# rf_exca.net
KiCad netlist of a schematic drawn in EAGLE
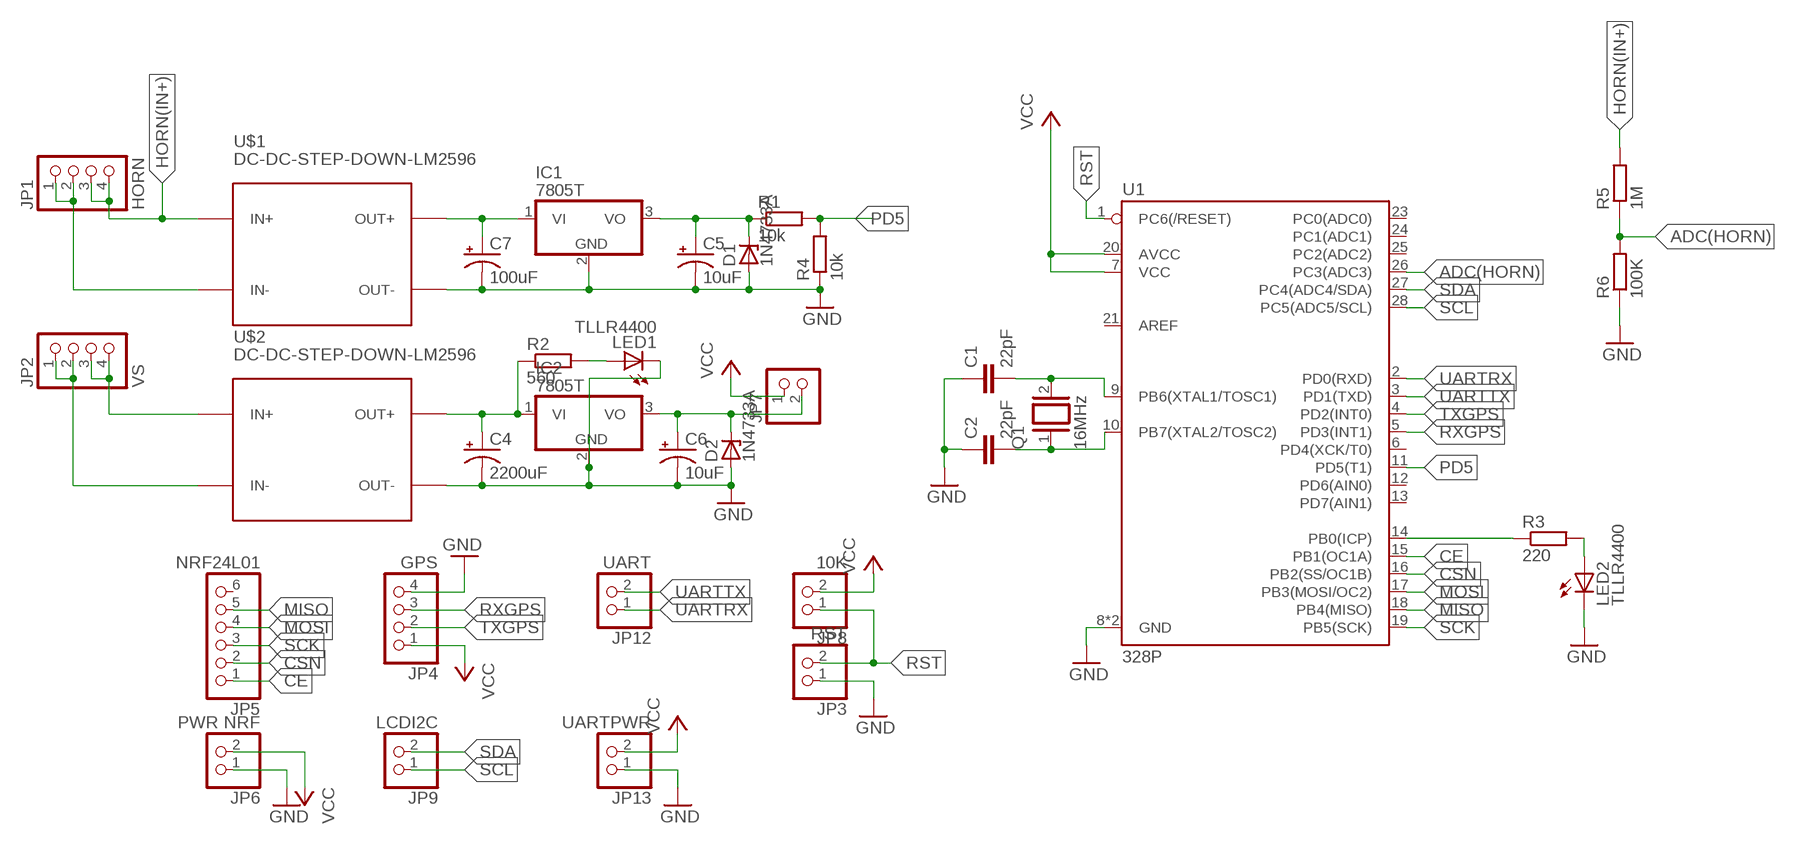
[diagram p0: schematic, sheet 1]

(export (version "E")
  (design (tool "Eeschema 10.0.6"))
  (components
    (comp (ref "C1")
      (value "22pF")
      (footprint "eagle-import:C025-024X044")
      (libsource (lib "eagle-import") (part "C-EU025-024X044"))
    )
    (comp (ref "C2")
      (value "22pF")
      (footprint "eagle-import:C025-024X044")
      (libsource (lib "eagle-import") (part "C-EU025-024X044"))
    )
    (comp (ref "C4")
      (value "2200uF")
      (footprint "eagle-import:E5-13")
      (libsource (lib "eagle-import") (part "CPOL-USE5-13"))
    )
    (comp (ref "C5")
      (value "10uF")
      (footprint "eagle-import:E2,5-6E")
      (libsource (lib "eagle-import") (part "CPOL-USE2,5-6E"))
    )
    (comp (ref "C6")
      (value "10uF")
      (footprint "eagle-import:E2,5-6E")
      (libsource (lib "eagle-import") (part "CPOL-USE2,5-6E"))
    )
    (comp (ref "C7")
      (value "100uF")
      (footprint "eagle-import:E2,5-7")
      (libsource (lib "eagle-import") (part "CPOL-USE2.5-7"))
    )
    (comp (ref "D1")
      (value "1N4733A")
      (footprint "eagle-import:DO41Z10")
      (libsource (lib "eagle-import") (part "1N4728"))
    )
    (comp (ref "D2")
      (value "1N4733A")
      (footprint "eagle-import:DO41Z10")
      (libsource (lib "eagle-import") (part "1N4728"))
    )
    (comp (ref "IC1")
      (value "7805T")
      (footprint "eagle-import:TO220H")
      (libsource (lib "eagle-import") (part "78T05"))
    )
    (comp (ref "IC2")
      (value "7805T")
      (footprint "eagle-import:TO220H")
      (libsource (lib "eagle-import") (part "78T05"))
    )
    (comp (ref "JP1")
      (value "HORN")
      (footprint "eagle-import:1X04")
      (libsource (lib "eagle-import") (part "PINHD-1X4"))
    )
    (comp (ref "JP2")
      (value "VS")
      (footprint "eagle-import:1X04")
      (libsource (lib "eagle-import") (part "PINHD-1X4"))
    )
    (comp (ref "JP3")
      (value "RST")
      (footprint "eagle-import:1X02")
      (libsource (lib "eagle-import") (part "PINHD-1X2"))
    )
    (comp (ref "JP4")
      (value "GPS")
      (footprint "eagle-import:1X04")
      (libsource (lib "eagle-import") (part "PINHD-1X4"))
    )
    (comp (ref "JP5")
      (value "NRF24L01")
      (footprint "eagle-import:1X06")
      (libsource (lib "eagle-import") (part "PINHD-1X6"))
    )
    (comp (ref "JP6")
      (value "PWR NRF")
      (footprint "eagle-import:1X02")
      (libsource (lib "eagle-import") (part "PINHD-1X2"))
    )
    (comp (ref "JP7")
      (value "PINHD-1X2")
      (footprint "eagle-import:1X02")
      (libsource (lib "eagle-import") (part "PINHD-1X2"))
    )
    (comp (ref "JP8")
      (value "10K")
      (footprint "eagle-import:1X02")
      (libsource (lib "eagle-import") (part "PINHD-1X2"))
    )
    (comp (ref "JP9")
      (value "LCDI2C")
      (footprint "eagle-import:1X02")
      (libsource (lib "eagle-import") (part "PINHD-1X2"))
    )
    (comp (ref "JP12")
      (value "UART")
      (footprint "eagle-import:1X02")
      (libsource (lib "eagle-import") (part "PINHD-1X2"))
    )
    (comp (ref "JP13")
      (value "UARTPWR")
      (footprint "eagle-import:1X02")
      (libsource (lib "eagle-import") (part "PINHD-1X2"))
    )
    (comp (ref "LED1")
      (value "TLLR4400")
      (footprint "eagle-import:LED3MM")
      (fields (field (name "MF") "VISHAY SEMICONDUCTOR"))
      (libsource (lib "eagle-import") (part "TLLR4400"))
    )
    (comp (ref "LED2")
      (value "TLLR4400")
      (footprint "eagle-import:LED3MM")
      (fields (field (name "MF") "VISHAY SEMICONDUCTOR"))
      (libsource (lib "eagle-import") (part "TLLR4400"))
    )
    (comp (ref "Q1")
      (value "16MHz")
      (footprint "eagle-import:QS")
      (libsource (lib "eagle-import") (part "XTAL/S"))
    )
    (comp (ref "R1")
      (value "10k")
      (footprint "eagle-import:0207_12")
      (libsource (lib "eagle-import") (part "R-EU_0207/12"))
    )
    (comp (ref "R2")
      (value "560")
      (footprint "eagle-import:0207_12")
      (libsource (lib "eagle-import") (part "R-EU_0207/12"))
    )
    (comp (ref "R3")
      (value "220")
      (footprint "eagle-import:0207_12")
      (libsource (lib "eagle-import") (part "R-EU_0207/12"))
    )
    (comp (ref "R4")
      (value "10k")
      (footprint "eagle-import:0207_12")
      (libsource (lib "eagle-import") (part "R-EU_0207/12"))
    )
    (comp (ref "R5")
      (value "1M")
      (footprint "eagle-import:0207_12")
      (libsource (lib "eagle-import") (part "R-EU_0207/12"))
    )
    (comp (ref "R6")
      (value "100K")
      (footprint "eagle-import:0207_12")
      (libsource (lib "eagle-import") (part "R-EU_0207/12"))
    )
    (comp (ref "U$1")
      (value "DC-DC-STEP-DOWN-LM2596")
      (footprint "eagle-import:DC-DC-STEP-DOWN-LM2596")
      (libsource (lib "eagle-import") (part "DC-DC-STEP-DOWN-LM2596"))
    )
    (comp (ref "U$2")
      (value "DC-DC-STEP-DOWN-LM2596")
      (footprint "eagle-import:DC-DC-STEP-DOWN-LM2596")
      (libsource (lib "eagle-import") (part "DC-DC-STEP-DOWN-LM2596"))
    )
    (comp (ref "U1")
      (value "328P")
      (footprint "eagle-import:DIP28")
      (libsource (lib "eagle-import") (part "ATMEGA328P_PDIP"))
    )
  )
  (nets
    (net (code "1") (name "ADC(HORN)") (class "Default")
      (node (ref "R5") (pin "1") (pinfunction "1_1") (pintype "passive"))
      (node (ref "R6") (pin "2") (pinfunction "2_2") (pintype "passive"))
      (node (ref "U1") (pin "26") (pinfunction "PC3(ADC3)_26") (pintype "bidirectional"))
    )
    (net (code "2") (name "CE") (class "Default")
      (node (ref "JP5") (pin "1") (pinfunction "1_1") (pintype "passive"))
      (node (ref "U1") (pin "15") (pinfunction "PB1(OC1A)_15") (pintype "bidirectional"))
    )
    (net (code "3") (name "CSN") (class "Default")
      (node (ref "JP5") (pin "2") (pinfunction "2_2") (pintype "passive"))
      (node (ref "U1") (pin "16") (pinfunction "PB2(SS/OC1B)_16") (pintype "bidirectional"))
    )
    (net (code "4") (name "GND") (class "Default")
      (node (ref "C1") (pin "1") (pinfunction "1_1") (pintype "passive"))
      (node (ref "C2") (pin "1") (pinfunction "1_1") (pintype "passive"))
      (node (ref "C4") (pin "-") (pinfunction "-_-") (pintype "passive"))
      (node (ref "C5") (pin "-") (pinfunction "-_-") (pintype "passive"))
      (node (ref "C6") (pin "-") (pinfunction "-_-") (pintype "passive"))
      (node (ref "C7") (pin "-") (pinfunction "-_-") (pintype "passive"))
      (node (ref "D1") (pin "A") (pinfunction "A_A") (pintype "passive"))
      (node (ref "D2") (pin "A") (pinfunction "A_A") (pintype "passive"))
      (node (ref "IC1") (pin "2") (pinfunction "GND_2") (pintype "passive"))
      (node (ref "IC2") (pin "2") (pinfunction "GND_2") (pintype "passive"))
      (node (ref "JP13") (pin "1") (pinfunction "1_1") (pintype "passive"))
      (node (ref "JP3") (pin "1") (pinfunction "1_1") (pintype "passive"))
      (node (ref "JP4") (pin "4") (pinfunction "4_4") (pintype "passive"))
      (node (ref "JP6") (pin "1") (pinfunction "1_1") (pintype "passive"))
      (node (ref "LED1") (pin "K") (pinfunction "C_K") (pintype "passive"))
      (node (ref "LED2") (pin "K") (pinfunction "C_K") (pintype "passive"))
      (node (ref "R4") (pin "1") (pinfunction "1_1") (pintype "passive"))
      (node (ref "R6") (pin "1") (pinfunction "1_1") (pintype "passive"))
      (node (ref "U$1") (pin "OUT-") (pinfunction "OUT-_OUT-") (pintype "bidirectional"))
      (node (ref "U$2") (pin "OUT-") (pinfunction "OUT-_OUT-") (pintype "bidirectional"))
      (node (ref "U1") (pin "22") (pinfunction "GND_22") (pintype "bidirectional"))
      (node (ref "U1") (pin "8") (pinfunction "GND_8") (pintype "bidirectional"))
    )
    (net (code "5") (name "HORN(IN+)") (class "Default")
      (node (ref "JP1") (pin "3") (pinfunction "3_3") (pintype "passive"))
      (node (ref "JP1") (pin "4") (pinfunction "4_4") (pintype "passive"))
      (node (ref "R5") (pin "2") (pinfunction "2_2") (pintype "passive"))
      (node (ref "U$1") (pin "IN+") (pinfunction "IN+_IN+") (pintype "bidirectional"))
    )
    (net (code "6") (name "MISO") (class "Default")
      (node (ref "JP5") (pin "5") (pinfunction "5_5") (pintype "passive"))
      (node (ref "U1") (pin "18") (pinfunction "PB4(MISO)_18") (pintype "bidirectional"))
    )
    (net (code "7") (name "MOSI") (class "Default")
      (node (ref "JP5") (pin "4") (pinfunction "4_4") (pintype "passive"))
      (node (ref "U1") (pin "17") (pinfunction "PB3(MOSI/OC2)_17") (pintype "bidirectional"))
    )
    (net (code "8") (name "Net-(IC1-VI)") (class "Default")
      (node (ref "C7") (pin "+") (pinfunction "+_+") (pintype "passive"))
      (node (ref "IC1") (pin "1") (pinfunction "VI_1") (pintype "input"))
      (node (ref "U$1") (pin "OUT+") (pinfunction "OUT+_OUT+") (pintype "bidirectional"))
    )
    (net (code "9") (name "Net-(IC1-VO)") (class "Default")
      (node (ref "C5") (pin "+") (pinfunction "+_+") (pintype "passive"))
      (node (ref "D1") (pin "C") (pinfunction "C_C") (pintype "passive"))
      (node (ref "IC1") (pin "3") (pinfunction "VO_3") (pintype "passive"))
      (node (ref "R1") (pin "1") (pinfunction "1_1") (pintype "passive"))
    )
    (net (code "10") (name "Net-(IC2-VI)") (class "Default")
      (node (ref "C4") (pin "+") (pinfunction "+_+") (pintype "passive"))
      (node (ref "IC2") (pin "1") (pinfunction "VI_1") (pintype "input"))
      (node (ref "R2") (pin "1") (pinfunction "1_1") (pintype "passive"))
      (node (ref "U$2") (pin "OUT+") (pinfunction "OUT+_OUT+") (pintype "bidirectional"))
    )
    (net (code "11") (name "Net-(IC2-VO)") (class "Default")
      (node (ref "C6") (pin "+") (pinfunction "+_+") (pintype "passive"))
      (node (ref "D2") (pin "C") (pinfunction "C_C") (pintype "passive"))
      (node (ref "IC2") (pin "3") (pinfunction "VO_3") (pintype "passive"))
      (node (ref "JP7") (pin "2") (pinfunction "2_2") (pintype "passive"))
    )
    (net (code "12") (name "Net-(JP1-Pad1)") (class "Default")
      (node (ref "JP1") (pin "1") (pinfunction "1_1") (pintype "passive"))
      (node (ref "JP1") (pin "2") (pinfunction "2_2") (pintype "passive"))
      (node (ref "U$1") (pin "IN-") (pinfunction "IN-_IN-") (pintype "bidirectional"))
    )
    (net (code "13") (name "Net-(JP2-Pad1)") (class "Default")
      (node (ref "JP2") (pin "1") (pinfunction "1_1") (pintype "passive"))
      (node (ref "JP2") (pin "2") (pinfunction "2_2") (pintype "passive"))
      (node (ref "U$2") (pin "IN-") (pinfunction "IN-_IN-") (pintype "bidirectional"))
    )
    (net (code "14") (name "Net-(JP2-Pad3)") (class "Default")
      (node (ref "JP2") (pin "3") (pinfunction "3_3") (pintype "passive"))
      (node (ref "JP2") (pin "4") (pinfunction "4_4") (pintype "passive"))
      (node (ref "U$2") (pin "IN+") (pinfunction "IN+_IN+") (pintype "bidirectional"))
    )
    (net (code "15") (name "Net-(LED1-PadA)") (class "Default")
      (node (ref "LED1") (pin "A") (pinfunction "A_A") (pintype "passive"))
      (node (ref "R2") (pin "2") (pinfunction "2_2") (pintype "passive"))
    )
    (net (code "16") (name "Net-(LED2-PadA)") (class "Default")
      (node (ref "LED2") (pin "A") (pinfunction "A_A") (pintype "passive"))
      (node (ref "R3") (pin "2") (pinfunction "2_2") (pintype "passive"))
    )
    (net (code "17") (name "Net-(U1-PB0(ICP))") (class "Default")
      (node (ref "R3") (pin "1") (pinfunction "1_1") (pintype "passive"))
      (node (ref "U1") (pin "14") (pinfunction "PB0(ICP)_14") (pintype "bidirectional"))
    )
    (net (code "18") (name "Net-(U1-PB6(XTAL1{slash}TOSC1))") (class "Default")
      (node (ref "C1") (pin "2") (pinfunction "2_2") (pintype "passive"))
      (node (ref "Q1") (pin "2") (pinfunction "2_2") (pintype "passive"))
      (node (ref "U1") (pin "9") (pinfunction "PB6(XTAL1/TOSC1)_9") (pintype "bidirectional"))
    )
    (net (code "19") (name "Net-(U1-PB7(XTAL2{slash}TOSC2))") (class "Default")
      (node (ref "C2") (pin "2") (pinfunction "2_2") (pintype "passive"))
      (node (ref "Q1") (pin "1") (pinfunction "1_1") (pintype "passive"))
      (node (ref "U1") (pin "10") (pinfunction "PB7(XTAL2/TOSC2)_10") (pintype "bidirectional"))
    )
    (net (code "20") (name "PD5") (class "Default")
      (node (ref "R1") (pin "2") (pinfunction "2_2") (pintype "passive"))
      (node (ref "R4") (pin "2") (pinfunction "2_2") (pintype "passive"))
      (node (ref "U1") (pin "11") (pinfunction "PD5(T1)_11") (pintype "bidirectional"))
    )
    (net (code "21") (name "RST") (class "Default")
      (node (ref "JP3") (pin "2") (pinfunction "2_2") (pintype "passive"))
      (node (ref "JP8") (pin "1") (pinfunction "1_1") (pintype "passive"))
      (node (ref "U1") (pin "1") (pinfunction "PC6(/RESET)_1") (pintype "bidirectional"))
    )
    (net (code "22") (name "RXGPS") (class "Default")
      (node (ref "JP4") (pin "3") (pinfunction "3_3") (pintype "passive"))
      (node (ref "U1") (pin "5") (pinfunction "PD3(INT1)_5") (pintype "bidirectional"))
    )
    (net (code "23") (name "SCK") (class "Default")
      (node (ref "JP5") (pin "3") (pinfunction "3_3") (pintype "passive"))
      (node (ref "U1") (pin "19") (pinfunction "PB5(SCK)_19") (pintype "bidirectional"))
    )
    (net (code "24") (name "SCL") (class "Default")
      (node (ref "JP9") (pin "1") (pinfunction "1_1") (pintype "passive"))
      (node (ref "U1") (pin "28") (pinfunction "PC5(ADC5/SCL)_28") (pintype "bidirectional"))
    )
    (net (code "25") (name "SDA") (class "Default")
      (node (ref "JP9") (pin "2") (pinfunction "2_2") (pintype "passive"))
      (node (ref "U1") (pin "27") (pinfunction "PC4(ADC4/SDA)_27") (pintype "bidirectional"))
    )
    (net (code "26") (name "TXGPS") (class "Default")
      (node (ref "JP4") (pin "2") (pinfunction "2_2") (pintype "passive"))
      (node (ref "U1") (pin "4") (pinfunction "PD2(INT0)_4") (pintype "bidirectional"))
    )
    (net (code "27") (name "UARTRX") (class "Default")
      (node (ref "JP12") (pin "1") (pinfunction "1_1") (pintype "passive"))
      (node (ref "U1") (pin "2") (pinfunction "PD0(RXD)_2") (pintype "bidirectional"))
    )
    (net (code "28") (name "UARTTX") (class "Default")
      (node (ref "JP12") (pin "2") (pinfunction "2_2") (pintype "passive"))
      (node (ref "U1") (pin "3") (pinfunction "PD1(TXD)_3") (pintype "bidirectional"))
    )
    (net (code "29") (name "VCC") (class "Default")
      (node (ref "JP13") (pin "2") (pinfunction "2_2") (pintype "passive"))
      (node (ref "JP4") (pin "1") (pinfunction "1_1") (pintype "passive"))
      (node (ref "JP6") (pin "2") (pinfunction "2_2") (pintype "passive"))
      (node (ref "JP7") (pin "1") (pinfunction "1_1") (pintype "passive"))
      (node (ref "JP8") (pin "2") (pinfunction "2_2") (pintype "passive"))
      (node (ref "U1") (pin "20") (pinfunction "AVCC_20") (pintype "bidirectional"))
      (node (ref "U1") (pin "7") (pinfunction "VCC_7") (pintype "bidirectional"))
    )
    (net (code "30") (name "unconnected-(JP5-Pad6)") (class "Default")
      (node (ref "JP5") (pin "6") (pinfunction "6_6") (pintype "passive"))
    )
    (net (code "31") (name "unconnected-(U1-AREF-Pad21)") (class "Default")
      (node (ref "U1") (pin "21") (pinfunction "AREF_21") (pintype "bidirectional"))
    )
    (net (code "32") (name "unconnected-(U1-PC0(ADC0)-Pad23)") (class "Default")
      (node (ref "U1") (pin "23") (pinfunction "PC0(ADC0)_23") (pintype "bidirectional"))
    )
    (net (code "33") (name "unconnected-(U1-PC1(ADC1)-Pad24)") (class "Default")
      (node (ref "U1") (pin "24") (pinfunction "PC1(ADC1)_24") (pintype "bidirectional"))
    )
    (net (code "34") (name "unconnected-(U1-PC2(ADC2)-Pad25)") (class "Default")
      (node (ref "U1") (pin "25") (pinfunction "PC2(ADC2)_25") (pintype "bidirectional"))
    )
    (net (code "35") (name "unconnected-(U1-PD4(XCK{slash}T0)-Pad6)") (class "Default")
      (node (ref "U1") (pin "6") (pinfunction "PD4(XCK/T0)_6") (pintype "bidirectional"))
    )
    (net (code "36") (name "unconnected-(U1-PD6(AIN0)-Pad12)") (class "Default")
      (node (ref "U1") (pin "12") (pinfunction "PD6(AIN0)_12") (pintype "bidirectional"))
    )
    (net (code "37") (name "unconnected-(U1-PD7(AIN1)-Pad13)") (class "Default")
      (node (ref "U1") (pin "13") (pinfunction "PD7(AIN1)_13") (pintype "bidirectional"))
    )
  )
)
